# 4_ADC_schdoc.net
KiCad netlist of a schematic drawn in Altium Designer
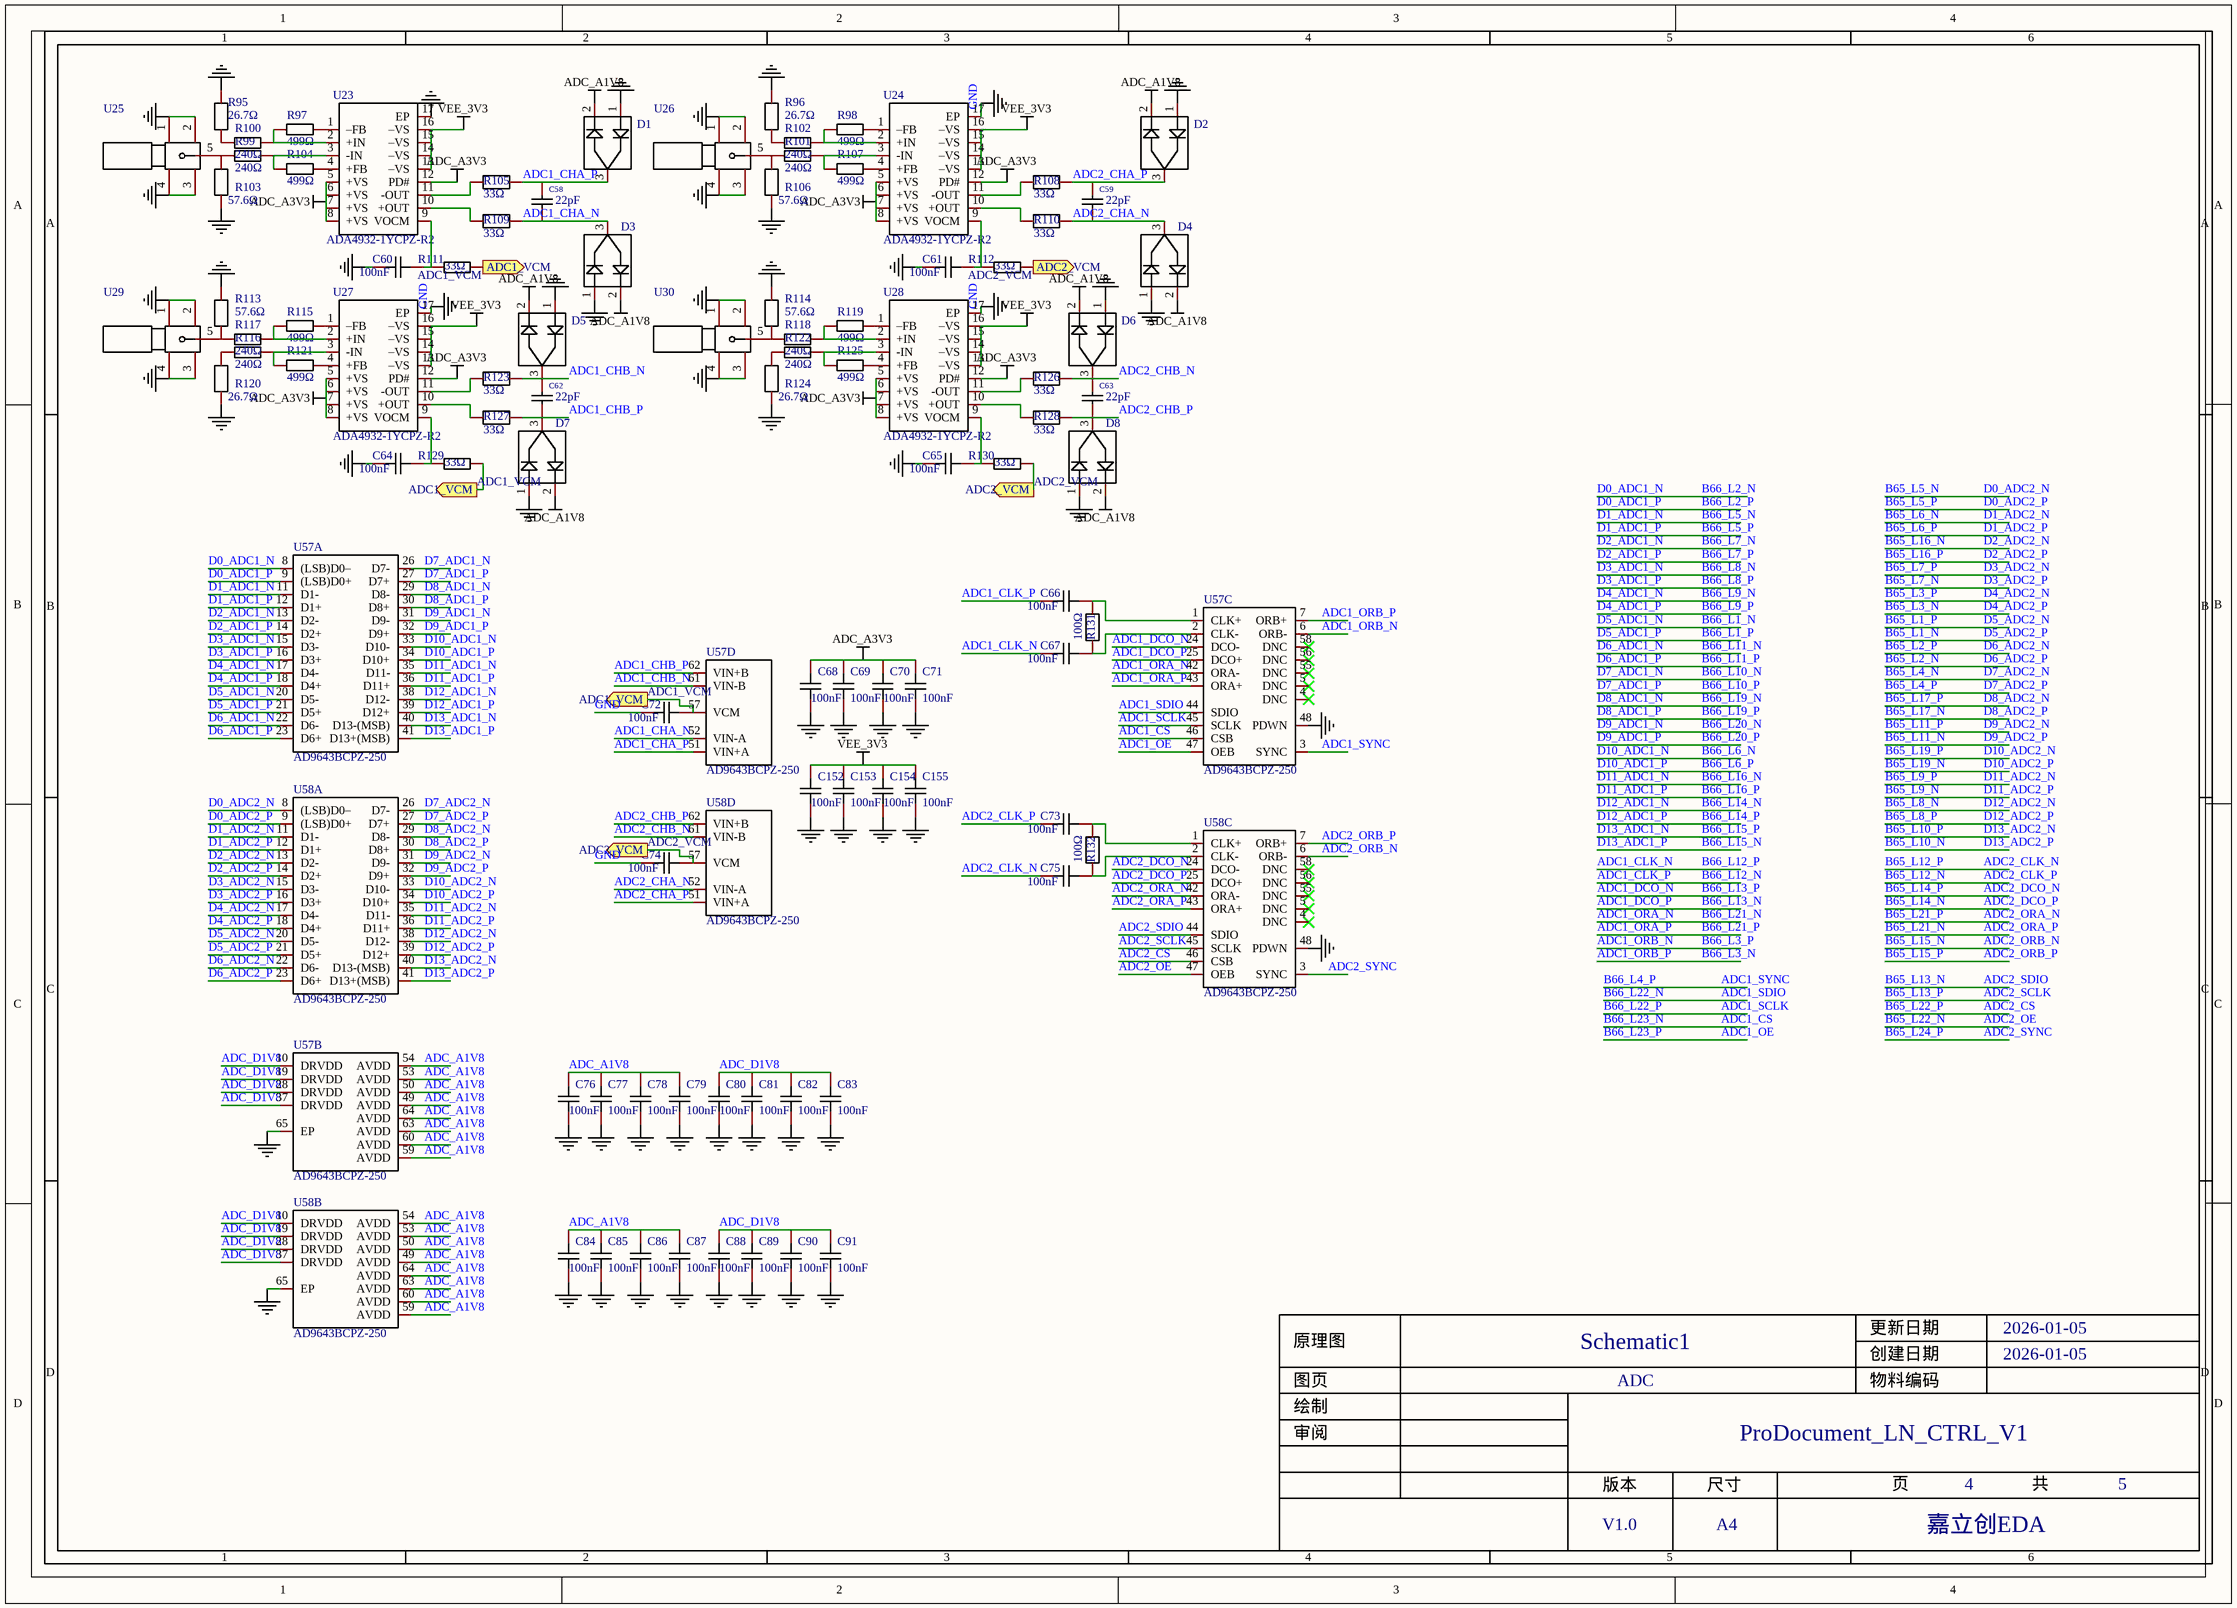
[diagram p0: 4_ADC.schdoc.schdoc]

(export (version "E")
  (design (tool "Eeschema 10.0.6"))
  (components
    (comp (ref "C58")
      (value "22pF")
      (fields
        (field (name "NAME") "22pF")
        (field (name "MANUFACTURER") "FH(风华)")
        (field (name "MANUFACTURER PART") "0402CG220J500NT")
        (field (name "TOLERANCE") "±5%")
      )
      (libsource (lib "altium-import") (part "root_1_0402CG220J500NT_"))
    )
    (comp (ref "C59")
      (value "22pF")
      (fields
        (field (name "NAME") "22pF")
        (field (name "MANUFACTURER") "FH(风华)")
        (field (name "MANUFACTURER PART") "0402CG220J500NT")
        (field (name "TOLERANCE") "±5%")
      )
      (libsource (lib "altium-import") (part "root_1_0402CG220J500NT_"))
    )
    (comp (ref "C60")
      (value "100nF")
      (fields
        (field (name "NAME") "100nF")
        (field (name "MANUFACTURER") "muRata(村田)")
        (field (name "MANUFACTURER PART") "GRM155R71H104KE14D")
        (field (name "TOLERANCE") "±10%")
      )
      (libsource (lib "altium-import") (part "root_2_GRM155R71H104KE14D_"))
    )
    (comp (ref "C61")
      (value "100nF")
      (fields
        (field (name "NAME") "100nF")
        (field (name "MANUFACTURER") "muRata(村田)")
        (field (name "MANUFACTURER PART") "GRM155R71H104KE14D")
        (field (name "TOLERANCE") "±10%")
      )
      (libsource (lib "altium-import") (part "root_2_GRM155R71H104KE14D_"))
    )
    (comp (ref "C62")
      (value "22pF")
      (fields
        (field (name "NAME") "22pF")
        (field (name "MANUFACTURER") "FH(风华)")
        (field (name "MANUFACTURER PART") "0402CG220J500NT")
        (field (name "TOLERANCE") "±5%")
      )
      (libsource (lib "altium-import") (part "root_1_0402CG220J500NT_"))
    )
    (comp (ref "C63")
      (value "22pF")
      (fields
        (field (name "NAME") "22pF")
        (field (name "MANUFACTURER") "FH(风华)")
        (field (name "MANUFACTURER PART") "0402CG220J500NT")
        (field (name "TOLERANCE") "±5%")
      )
      (libsource (lib "altium-import") (part "root_1_0402CG220J500NT_"))
    )
    (comp (ref "C64")
      (value "100nF")
      (fields
        (field (name "NAME") "100nF")
        (field (name "MANUFACTURER") "muRata(村田)")
        (field (name "MANUFACTURER PART") "GRM155R71H104KE14D")
        (field (name "TOLERANCE") "±10%")
      )
      (libsource (lib "altium-import") (part "root_2_GRM155R71H104KE14D_"))
    )
    (comp (ref "C65")
      (value "100nF")
      (fields
        (field (name "NAME") "100nF")
        (field (name "MANUFACTURER") "muRata(村田)")
        (field (name "MANUFACTURER PART") "GRM155R71H104KE14D")
        (field (name "TOLERANCE") "±10%")
      )
      (libsource (lib "altium-import") (part "root_2_GRM155R71H104KE14D_"))
    )
    (comp (ref "C66")
      (value "100nF")
      (fields
        (field (name "NAME") "100nF")
        (field (name "MANUFACTURER") "muRata(村田)")
        (field (name "MANUFACTURER PART") "GRM155R71H104KE14D")
        (field (name "TOLERANCE") "±10%")
      )
      (libsource (lib "altium-import") (part "root_2_GRM155R71H104KE14D_"))
    )
    (comp (ref "C67")
      (value "100nF")
      (fields
        (field (name "NAME") "100nF")
        (field (name "MANUFACTURER") "muRata(村田)")
        (field (name "MANUFACTURER PART") "GRM155R71H104KE14D")
        (field (name "TOLERANCE") "±10%")
      )
      (libsource (lib "altium-import") (part "root_2_GRM155R71H104KE14D_"))
    )
    (comp (ref "C68")
      (value "100nF")
      (fields
        (field (name "NAME") "100nF")
        (field (name "MANUFACTURER") "muRata(村田)")
        (field (name "MANUFACTURER PART") "GRM155R71H104KE14D")
        (field (name "TOLERANCE") "±10%")
      )
      (libsource (lib "altium-import") (part "root_1_GRM155R71H104KE14D_"))
    )
    (comp (ref "C69")
      (value "100nF")
      (fields
        (field (name "NAME") "100nF")
        (field (name "MANUFACTURER") "muRata(村田)")
        (field (name "MANUFACTURER PART") "GRM155R71H104KE14D")
        (field (name "TOLERANCE") "±10%")
      )
      (libsource (lib "altium-import") (part "root_1_GRM155R71H104KE14D_"))
    )
    (comp (ref "C70")
      (value "100nF")
      (fields
        (field (name "NAME") "100nF")
        (field (name "MANUFACTURER") "muRata(村田)")
        (field (name "MANUFACTURER PART") "GRM155R71H104KE14D")
        (field (name "TOLERANCE") "±10%")
      )
      (libsource (lib "altium-import") (part "root_1_GRM155R71H104KE14D_"))
    )
    (comp (ref "C71")
      (value "100nF")
      (fields
        (field (name "NAME") "100nF")
        (field (name "MANUFACTURER") "muRata(村田)")
        (field (name "MANUFACTURER PART") "GRM155R71H104KE14D")
        (field (name "TOLERANCE") "±10%")
      )
      (libsource (lib "altium-import") (part "root_1_GRM155R71H104KE14D_"))
    )
    (comp (ref "C72")
      (value "100nF")
      (fields
        (field (name "NAME") "100nF")
        (field (name "MANUFACTURER") "muRata(村田)")
        (field (name "MANUFACTURER PART") "GRM155R71H104KE14D")
        (field (name "TOLERANCE") "±10%")
      )
      (libsource (lib "altium-import") (part "root_2_GRM155R71H104KE14D_"))
    )
    (comp (ref "C73")
      (value "100nF")
      (fields
        (field (name "NAME") "100nF")
        (field (name "MANUFACTURER") "muRata(村田)")
        (field (name "MANUFACTURER PART") "GRM155R71H104KE14D")
        (field (name "TOLERANCE") "±10%")
      )
      (libsource (lib "altium-import") (part "root_2_GRM155R71H104KE14D_"))
    )
    (comp (ref "C74")
      (value "100nF")
      (fields
        (field (name "NAME") "100nF")
        (field (name "MANUFACTURER") "muRata(村田)")
        (field (name "MANUFACTURER PART") "GRM155R71H104KE14D")
        (field (name "TOLERANCE") "±10%")
      )
      (libsource (lib "altium-import") (part "root_2_GRM155R71H104KE14D_"))
    )
    (comp (ref "C75")
      (value "100nF")
      (fields
        (field (name "NAME") "100nF")
        (field (name "MANUFACTURER") "muRata(村田)")
        (field (name "MANUFACTURER PART") "GRM155R71H104KE14D")
        (field (name "TOLERANCE") "±10%")
      )
      (libsource (lib "altium-import") (part "root_2_GRM155R71H104KE14D_"))
    )
    (comp (ref "C76")
      (value "100nF")
      (fields
        (field (name "NAME") "100nF")
        (field (name "MANUFACTURER") "muRata(村田)")
        (field (name "MANUFACTURER PART") "GRM155R71H104KE14D")
        (field (name "TOLERANCE") "±10%")
      )
      (libsource (lib "altium-import") (part "root_1_GRM155R71H104KE14D_"))
    )
    (comp (ref "C77")
      (value "100nF")
      (fields
        (field (name "NAME") "100nF")
        (field (name "MANUFACTURER") "muRata(村田)")
        (field (name "MANUFACTURER PART") "GRM155R71H104KE14D")
        (field (name "TOLERANCE") "±10%")
      )
      (libsource (lib "altium-import") (part "root_1_GRM155R71H104KE14D_"))
    )
    (comp (ref "C78")
      (value "100nF")
      (fields
        (field (name "NAME") "100nF")
        (field (name "MANUFACTURER") "muRata(村田)")
        (field (name "MANUFACTURER PART") "GRM155R71H104KE14D")
        (field (name "TOLERANCE") "±10%")
      )
      (libsource (lib "altium-import") (part "root_1_GRM155R71H104KE14D_"))
    )
    (comp (ref "C79")
      (value "100nF")
      (fields
        (field (name "NAME") "100nF")
        (field (name "MANUFACTURER") "muRata(村田)")
        (field (name "MANUFACTURER PART") "GRM155R71H104KE14D")
        (field (name "TOLERANCE") "±10%")
      )
      (libsource (lib "altium-import") (part "root_1_GRM155R71H104KE14D_"))
    )
    (comp (ref "C80")
      (value "100nF")
      (fields
        (field (name "NAME") "100nF")
        (field (name "MANUFACTURER") "muRata(村田)")
        (field (name "MANUFACTURER PART") "GRM155R71H104KE14D")
        (field (name "TOLERANCE") "±10%")
      )
      (libsource (lib "altium-import") (part "root_1_GRM155R71H104KE14D_"))
    )
    (comp (ref "C81")
      (value "100nF")
      (fields
        (field (name "NAME") "100nF")
        (field (name "MANUFACTURER") "muRata(村田)")
        (field (name "MANUFACTURER PART") "GRM155R71H104KE14D")
        (field (name "TOLERANCE") "±10%")
      )
      (libsource (lib "altium-import") (part "root_1_GRM155R71H104KE14D_"))
    )
    (comp (ref "C82")
      (value "100nF")
      (fields
        (field (name "NAME") "100nF")
        (field (name "MANUFACTURER") "muRata(村田)")
        (field (name "MANUFACTURER PART") "GRM155R71H104KE14D")
        (field (name "TOLERANCE") "±10%")
      )
      (libsource (lib "altium-import") (part "root_1_GRM155R71H104KE14D_"))
    )
    (comp (ref "C83")
      (value "100nF")
      (fields
        (field (name "NAME") "100nF")
        (field (name "MANUFACTURER") "muRata(村田)")
        (field (name "MANUFACTURER PART") "GRM155R71H104KE14D")
        (field (name "TOLERANCE") "±10%")
      )
      (libsource (lib "altium-import") (part "root_1_GRM155R71H104KE14D_"))
    )
    (comp (ref "C84")
      (value "100nF")
      (fields
        (field (name "NAME") "100nF")
        (field (name "MANUFACTURER") "muRata(村田)")
        (field (name "MANUFACTURER PART") "GRM155R71H104KE14D")
        (field (name "TOLERANCE") "±10%")
      )
      (libsource (lib "altium-import") (part "root_1_GRM155R71H104KE14D_"))
    )
    (comp (ref "C85")
      (value "100nF")
      (fields
        (field (name "NAME") "100nF")
        (field (name "MANUFACTURER") "muRata(村田)")
        (field (name "MANUFACTURER PART") "GRM155R71H104KE14D")
        (field (name "TOLERANCE") "±10%")
      )
      (libsource (lib "altium-import") (part "root_1_GRM155R71H104KE14D_"))
    )
    (comp (ref "C86")
      (value "100nF")
      (fields
        (field (name "NAME") "100nF")
        (field (name "MANUFACTURER") "muRata(村田)")
        (field (name "MANUFACTURER PART") "GRM155R71H104KE14D")
        (field (name "TOLERANCE") "±10%")
      )
      (libsource (lib "altium-import") (part "root_1_GRM155R71H104KE14D_"))
    )
    (comp (ref "C87")
      (value "100nF")
      (fields
        (field (name "NAME") "100nF")
        (field (name "MANUFACTURER") "muRata(村田)")
        (field (name "MANUFACTURER PART") "GRM155R71H104KE14D")
        (field (name "TOLERANCE") "±10%")
      )
      (libsource (lib "altium-import") (part "root_1_GRM155R71H104KE14D_"))
    )
    (comp (ref "C88")
      (value "100nF")
      (fields
        (field (name "NAME") "100nF")
        (field (name "MANUFACTURER") "muRata(村田)")
        (field (name "MANUFACTURER PART") "GRM155R71H104KE14D")
        (field (name "TOLERANCE") "±10%")
      )
      (libsource (lib "altium-import") (part "root_1_GRM155R71H104KE14D_"))
    )
    (comp (ref "C89")
      (value "100nF")
      (fields
        (field (name "NAME") "100nF")
        (field (name "MANUFACTURER") "muRata(村田)")
        (field (name "MANUFACTURER PART") "GRM155R71H104KE14D")
        (field (name "TOLERANCE") "±10%")
      )
      (libsource (lib "altium-import") (part "root_1_GRM155R71H104KE14D_"))
    )
    (comp (ref "C90")
      (value "100nF")
      (fields
        (field (name "NAME") "100nF")
        (field (name "MANUFACTURER") "muRata(村田)")
        (field (name "MANUFACTURER PART") "GRM155R71H104KE14D")
        (field (name "TOLERANCE") "±10%")
      )
      (libsource (lib "altium-import") (part "root_1_GRM155R71H104KE14D_"))
    )
    (comp (ref "C91")
      (value "100nF")
      (fields
        (field (name "NAME") "100nF")
        (field (name "MANUFACTURER") "muRata(村田)")
        (field (name "MANUFACTURER PART") "GRM155R71H104KE14D")
        (field (name "TOLERANCE") "±10%")
      )
      (libsource (lib "altium-import") (part "root_1_GRM155R71H104KE14D_"))
    )
    (comp (ref "C152")
      (value "100nF")
      (fields
        (field (name "NAME") "100nF")
        (field (name "MANUFACTURER") "muRata(村田)")
        (field (name "MANUFACTURER PART") "GRM155R71H104KE14D")
        (field (name "TOLERANCE") "±10%")
      )
      (libsource (lib "altium-import") (part "root_1_GRM155R71H104KE14D_"))
    )
    (comp (ref "C153")
      (value "100nF")
      (fields
        (field (name "NAME") "100nF")
        (field (name "MANUFACTURER") "muRata(村田)")
        (field (name "MANUFACTURER PART") "GRM155R71H104KE14D")
        (field (name "TOLERANCE") "±10%")
      )
      (libsource (lib "altium-import") (part "root_1_GRM155R71H104KE14D_"))
    )
    (comp (ref "C154")
      (value "100nF")
      (fields
        (field (name "NAME") "100nF")
        (field (name "MANUFACTURER") "muRata(村田)")
        (field (name "MANUFACTURER PART") "GRM155R71H104KE14D")
        (field (name "TOLERANCE") "±10%")
      )
      (libsource (lib "altium-import") (part "root_1_GRM155R71H104KE14D_"))
    )
    (comp (ref "C155")
      (value "100nF")
      (fields
        (field (name "NAME") "100nF")
        (field (name "MANUFACTURER") "muRata(村田)")
        (field (name "MANUFACTURER PART") "GRM155R71H104KE14D")
        (field (name "TOLERANCE") "±10%")
      )
      (libsource (lib "altium-import") (part "root_1_GRM155R71H104KE14D_"))
    )
    (comp (ref "D1")
      (value "NSVR351SDSA3T1G")
      (description "二极管配置:1对串联式;正向压降(Vf):230mV@1mA;直流反向耐压(Vr):5V;整流电流:30mA;")
      (fields (field (name "MANUFACTURER") "onsemi(安森美)"))
      (libsource (lib "altium-import") (part "root_3_NSVR351SDSA3T1G_"))
    )
    (comp (ref "D2")
      (value "NSVR351SDSA3T1G")
      (description "二极管配置:1对串联式;正向压降(Vf):230mV@1mA;直流反向耐压(Vr):5V;整流电流:30mA;")
      (fields (field (name "MANUFACTURER") "onsemi(安森美)"))
      (libsource (lib "altium-import") (part "root_3_NSVR351SDSA3T1G_"))
    )
    (comp (ref "D3")
      (value "NSVR351SDSA3T1G")
      (description "二极管配置:1对串联式;正向压降(Vf):230mV@1mA;直流反向耐压(Vr):5V;整流电流:30mA;")
      (fields (field (name "MANUFACTURER") "onsemi(安森美)"))
      (libsource (lib "altium-import") (part "root_1_NSVR351SDSA3T1G_"))
    )
    (comp (ref "D4")
      (value "NSVR351SDSA3T1G")
      (description "二极管配置:1对串联式;正向压降(Vf):230mV@1mA;直流反向耐压(Vr):5V;整流电流:30mA;")
      (fields (field (name "MANUFACTURER") "onsemi(安森美)"))
      (libsource (lib "altium-import") (part "root_1_NSVR351SDSA3T1G_"))
    )
    (comp (ref "D5")
      (value "NSVR351SDSA3T1G")
      (description "二极管配置:1对串联式;正向压降(Vf):230mV@1mA;直流反向耐压(Vr):5V;整流电流:30mA;")
      (fields (field (name "MANUFACTURER") "onsemi(安森美)"))
      (libsource (lib "altium-import") (part "root_3_NSVR351SDSA3T1G_"))
    )
    (comp (ref "D6")
      (value "NSVR351SDSA3T1G")
      (description "二极管配置:1对串联式;正向压降(Vf):230mV@1mA;直流反向耐压(Vr):5V;整流电流:30mA;")
      (fields (field (name "MANUFACTURER") "onsemi(安森美)"))
      (libsource (lib "altium-import") (part "root_3_NSVR351SDSA3T1G_"))
    )
    (comp (ref "D7")
      (value "NSVR351SDSA3T1G")
      (description "二极管配置:1对串联式;正向压降(Vf):230mV@1mA;直流反向耐压(Vr):5V;整流电流:30mA;")
      (fields (field (name "MANUFACTURER") "onsemi(安森美)"))
      (libsource (lib "altium-import") (part "root_1_NSVR351SDSA3T1G_"))
    )
    (comp (ref "D8")
      (value "NSVR351SDSA3T1G")
      (description "二极管配置:1对串联式;正向压降(Vf):230mV@1mA;直流反向耐压(Vr):5V;整流电流:30mA;")
      (fields (field (name "MANUFACTURER") "onsemi(安森美)"))
      (libsource (lib "altium-import") (part "root_1_NSVR351SDSA3T1G_"))
    )
    (comp (ref "R95")
      (value "26.7Ω")
      (description "阻值:1kΩ;精度:±0.1%;温度系数:±25ppm/;")
      (fields (field (name "MANUFACTURER") "Viking(光颉)") (field (name "MANUFACTURER PART") "ARG02BTC1001"))
      (libsource (lib "altium-import") (part "root_3_ARG02BTC1001_"))
    )
    (comp (ref "R96")
      (value "26.7Ω")
      (description "阻值:1kΩ;精度:±0.1%;温度系数:±25ppm/;")
      (fields (field (name "MANUFACTURER") "Viking(光颉)") (field (name "MANUFACTURER PART") "ARG02BTC1001"))
      (libsource (lib "altium-import") (part "root_1_ARG02BTC1001_"))
    )
    (comp (ref "R97")
      (value "499Ω")
      (fields
        (field (name "NAME") "499Ω")
        (field (name "MANUFACTURER") "UNI-ROYAL(厚声)")
        (field (name "MANUFACTURER PART") "0402WGF4990TCE")
        (field (name "TOLERANCE") "±1%")
      )
      (libsource (lib "altium-import") (part "root_0_0402WGF4990TCE_"))
    )
    (comp (ref "R98")
      (value "499Ω")
      (fields
        (field (name "NAME") "499Ω")
        (field (name "MANUFACTURER") "UNI-ROYAL(厚声)")
        (field (name "MANUFACTURER PART") "0402WGF4990TCE")
        (field (name "TOLERANCE") "±1%")
      )
      (libsource (lib "altium-import") (part "root_0_0402WGF4990TCE_"))
    )
    (comp (ref "R99")
      (value "240Ω")
      (fields
        (field (name "NAME") "240Ω")
        (field (name "MANUFACTURER") "UNI-ROYAL(厚声)")
        (field (name "MANUFACTURER PART") "0402WGF2400TCE")
        (field (name "TOLERANCE") "±1%")
      )
      (libsource (lib "altium-import") (part "root_0_0402WGF2400TCE_"))
    )
    (comp (ref "R100")
      (value "240Ω")
      (fields
        (field (name "NAME") "240Ω")
        (field (name "MANUFACTURER") "UNI-ROYAL(厚声)")
        (field (name "MANUFACTURER PART") "0402WGF2400TCE")
        (field (name "TOLERANCE") "±1%")
      )
      (libsource (lib "altium-import") (part "root_0_0402WGF2400TCE_"))
    )
    (comp (ref "R101")
      (value "240Ω")
      (fields
        (field (name "NAME") "240Ω")
        (field (name "MANUFACTURER") "UNI-ROYAL(厚声)")
        (field (name "MANUFACTURER PART") "0402WGF2400TCE")
        (field (name "TOLERANCE") "±1%")
      )
      (libsource (lib "altium-import") (part "root_0_0402WGF2400TCE_"))
    )
    (comp (ref "R102")
      (value "240Ω")
      (fields
        (field (name "NAME") "240Ω")
        (field (name "MANUFACTURER") "UNI-ROYAL(厚声)")
        (field (name "MANUFACTURER PART") "0402WGF2400TCE")
        (field (name "TOLERANCE") "±1%")
      )
      (libsource (lib "altium-import") (part "root_0_0402WGF2400TCE_"))
    )
    (comp (ref "R103")
      (value "57.6Ω")
      (description "阻值:1kΩ;精度:±0.1%;温度系数:±25ppm/;")
      (fields (field (name "MANUFACTURER") "Viking(光颉)") (field (name "MANUFACTURER PART") "ARG02BTC1001"))
      (libsource (lib "altium-import") (part "root_3_ARG02BTC1001_"))
    )
    (comp (ref "R104")
      (value "499Ω")
      (fields
        (field (name "NAME") "499Ω")
        (field (name "MANUFACTURER") "UNI-ROYAL(厚声)")
        (field (name "MANUFACTURER PART") "0402WGF4990TCE")
        (field (name "TOLERANCE") "±1%")
      )
      (libsource (lib "altium-import") (part "root_0_0402WGF4990TCE_"))
    )
    (comp (ref "R105")
      (value "33Ω")
      (description "阻值:1kΩ;精度:±0.1%;温度系数:±25ppm/;")
      (fields (field (name "MANUFACTURER") "Viking(光颉)") (field (name "MANUFACTURER PART") "ARG02BTC1001"))
      (libsource (lib "altium-import") (part "root_2_ARG02BTC1001_"))
    )
    (comp (ref "R106")
      (value "57.6Ω")
      (description "阻值:1kΩ;精度:±0.1%;温度系数:±25ppm/;")
      (fields (field (name "MANUFACTURER") "Viking(光颉)") (field (name "MANUFACTURER PART") "ARG02BTC1001"))
      (libsource (lib "altium-import") (part "root_1_ARG02BTC1001_"))
    )
    (comp (ref "R107")
      (value "499Ω")
      (fields
        (field (name "NAME") "499Ω")
        (field (name "MANUFACTURER") "UNI-ROYAL(厚声)")
        (field (name "MANUFACTURER PART") "0402WGF4990TCE")
        (field (name "TOLERANCE") "±1%")
      )
      (libsource (lib "altium-import") (part "root_0_0402WGF4990TCE_"))
    )
    (comp (ref "R108")
      (value "33Ω")
      (description "阻值:1kΩ;精度:±0.1%;温度系数:±25ppm/;")
      (fields (field (name "MANUFACTURER") "Viking(光颉)") (field (name "MANUFACTURER PART") "ARG02BTC1001"))
      (libsource (lib "altium-import") (part "root_2_ARG02BTC1001_"))
    )
    (comp (ref "R109")
      (value "33Ω")
      (description "阻值:1kΩ;精度:±0.1%;温度系数:±25ppm/;")
      (fields (field (name "MANUFACTURER") "Viking(光颉)") (field (name "MANUFACTURER PART") "ARG02BTC1001"))
      (libsource (lib "altium-import") (part "root_2_ARG02BTC1001_"))
    )
    (comp (ref "R110")
      (value "33Ω")
      (description "阻值:1kΩ;精度:±0.1%;温度系数:±25ppm/;")
      (fields (field (name "MANUFACTURER") "Viking(光颉)") (field (name "MANUFACTURER PART") "ARG02BTC1001"))
      (libsource (lib "altium-import") (part "root_2_ARG02BTC1001_"))
    )
    (comp (ref "R111")
      (value "33Ω")
      (fields
        (field (name "NAME") "33Ω")
        (field (name "MANUFACTURER") "UNI-ROYAL(厚声)")
        (field (name "MANUFACTURER PART") "0402WGF330JTCE")
        (field (name "TOLERANCE") "±1%")
      )
      (libsource (lib "altium-import") (part "root_0_0402WGF330JTCE_"))
    )
    (comp (ref "R112")
      (value "33Ω")
      (fields
        (field (name "NAME") "33Ω")
        (field (name "MANUFACTURER") "UNI-ROYAL(厚声)")
        (field (name "MANUFACTURER PART") "0402WGF330JTCE")
        (field (name "TOLERANCE") "±1%")
      )
      (libsource (lib "altium-import") (part "root_0_0402WGF330JTCE_"))
    )
    (comp (ref "R113")
      (value "57.6Ω")
      (description "阻值:1kΩ;精度:±0.1%;温度系数:±25ppm/;")
      (fields (field (name "MANUFACTURER") "Viking(光颉)") (field (name "MANUFACTURER PART") "ARG02BTC1001"))
      (libsource (lib "altium-import") (part "root_1_ARG02BTC1001_"))
    )
    (comp (ref "R114")
      (value "57.6Ω")
      (description "阻值:1kΩ;精度:±0.1%;温度系数:±25ppm/;")
      (fields (field (name "MANUFACTURER") "Viking(光颉)") (field (name "MANUFACTURER PART") "ARG02BTC1001"))
      (libsource (lib "altium-import") (part "root_1_ARG02BTC1001_"))
    )
    (comp (ref "R115")
      (value "499Ω")
      (fields
        (field (name "NAME") "499Ω")
        (field (name "MANUFACTURER") "UNI-ROYAL(厚声)")
        (field (name "MANUFACTURER PART") "0402WGF4990TCE")
        (field (name "TOLERANCE") "±1%")
      )
      (libsource (lib "altium-import") (part "root_0_0402WGF4990TCE_"))
    )
    (comp (ref "R116")
      (value "240Ω")
      (fields
        (field (name "NAME") "240Ω")
        (field (name "MANUFACTURER") "UNI-ROYAL(厚声)")
        (field (name "MANUFACTURER PART") "0402WGF2400TCE")
        (field (name "TOLERANCE") "±1%")
      )
      (libsource (lib "altium-import") (part "root_0_0402WGF2400TCE_"))
    )
    (comp (ref "R117")
      (value "240Ω")
      (fields
        (field (name "NAME") "240Ω")
        (field (name "MANUFACTURER") "UNI-ROYAL(厚声)")
        (field (name "MANUFACTURER PART") "0402WGF2400TCE")
        (field (name "TOLERANCE") "±1%")
      )
      (libsource (lib "altium-import") (part "root_0_0402WGF2400TCE_"))
    )
    (comp (ref "R118")
      (value "240Ω")
      (fields
        (field (name "NAME") "240Ω")
        (field (name "MANUFACTURER") "UNI-ROYAL(厚声)")
        (field (name "MANUFACTURER PART") "0402WGF2400TCE")
        (field (name "TOLERANCE") "±1%")
      )
      (libsource (lib "altium-import") (part "root_0_0402WGF2400TCE_"))
    )
    (comp (ref "R119")
      (value "499Ω")
      (fields
        (field (name "NAME") "499Ω")
        (field (name "MANUFACTURER") "UNI-ROYAL(厚声)")
        (field (name "MANUFACTURER PART") "0402WGF4990TCE")
        (field (name "TOLERANCE") "±1%")
      )
      (libsource (lib "altium-import") (part "root_0_0402WGF4990TCE_"))
    )
    (comp (ref "R120")
      (value "26.7Ω")
      (description "阻值:1kΩ;精度:±0.1%;温度系数:±25ppm/;")
      (fields (field (name "MANUFACTURER") "Viking(光颉)") (field (name "MANUFACTURER PART") "ARG02BTC1001"))
      (libsource (lib "altium-import") (part "root_1_ARG02BTC1001_"))
    )
    (comp (ref "R121")
      (value "499Ω")
      (fields
        (field (name "NAME") "499Ω")
        (field (name "MANUFACTURER") "UNI-ROYAL(厚声)")
        (field (name "MANUFACTURER PART") "0402WGF4990TCE")
        (field (name "TOLERANCE") "±1%")
      )
      (libsource (lib "altium-import") (part "root_0_0402WGF4990TCE_"))
    )
    (comp (ref "R122")
      (value "240Ω")
      (fields
        (field (name "NAME") "240Ω")
        (field (name "MANUFACTURER") "UNI-ROYAL(厚声)")
        (field (name "MANUFACTURER PART") "0402WGF2400TCE")
        (field (name "TOLERANCE") "±1%")
      )
      (libsource (lib "altium-import") (part "root_0_0402WGF2400TCE_"))
    )
    (comp (ref "R123")
      (value "33Ω")
      (description "阻值:1kΩ;精度:±0.1%;温度系数:±25ppm/;")
      (fields (field (name "MANUFACTURER") "Viking(光颉)") (field (name "MANUFACTURER PART") "ARG02BTC1001"))
      (libsource (lib "altium-import") (part "root_2_ARG02BTC1001_"))
    )
    (comp (ref "R124")
      (value "26.7Ω")
      (description "阻值:1kΩ;精度:±0.1%;温度系数:±25ppm/;")
      (fields (field (name "MANUFACTURER") "Viking(光颉)") (field (name "MANUFACTURER PART") "ARG02BTC1001"))
      (libsource (lib "altium-import") (part "root_1_ARG02BTC1001_"))
    )
    (comp (ref "R125")
      (value "499Ω")
      (fields
        (field (name "NAME") "499Ω")
        (field (name "MANUFACTURER") "UNI-ROYAL(厚声)")
        (field (name "MANUFACTURER PART") "0402WGF4990TCE")
        (field (name "TOLERANCE") "±1%")
      )
      (libsource (lib "altium-import") (part "root_0_0402WGF4990TCE_"))
    )
    (comp (ref "R126")
      (value "33Ω")
      (description "阻值:1kΩ;精度:±0.1%;温度系数:±25ppm/;")
      (fields (field (name "MANUFACTURER") "Viking(光颉)") (field (name "MANUFACTURER PART") "ARG02BTC1001"))
      (libsource (lib "altium-import") (part "root_2_ARG02BTC1001_"))
    )
    (comp (ref "R127")
      (value "33Ω")
      (description "阻值:1kΩ;精度:±0.1%;温度系数:±25ppm/;")
      (fields (field (name "MANUFACTURER") "Viking(光颉)") (field (name "MANUFACTURER PART") "ARG02BTC1001"))
      (libsource (lib "altium-import") (part "root_2_ARG02BTC1001_"))
    )
    (comp (ref "R128")
      (value "33Ω")
      (description "阻值:1kΩ;精度:±0.1%;温度系数:±25ppm/;")
      (fields (field (name "MANUFACTURER") "Viking(光颉)") (field (name "MANUFACTURER PART") "ARG02BTC1001"))
      (libsource (lib "altium-import") (part "root_2_ARG02BTC1001_"))
    )
    (comp (ref "R129")
      (value "33Ω")
      (fields
        (field (name "NAME") "33Ω")
        (field (name "MANUFACTURER") "UNI-ROYAL(厚声)")
        (field (name "MANUFACTURER PART") "0402WGF330JTCE")
        (field (name "TOLERANCE") "±1%")
      )
      (libsource (lib "altium-import") (part "root_0_0402WGF330JTCE_"))
    )
    (comp (ref "R130")
      (value "33Ω")
      (fields
        (field (name "NAME") "33Ω")
        (field (name "MANUFACTURER") "UNI-ROYAL(厚声)")
        (field (name "MANUFACTURER PART") "0402WGF330JTCE")
        (field (name "TOLERANCE") "±1%")
      )
      (libsource (lib "altium-import") (part "root_0_0402WGF330JTCE_"))
    )
    (comp (ref "R131")
      (value "100Ω")
      (fields
        (field (name "NAME") "100Ω")
        (field (name "MANUFACTURER") "YAGEO(国巨)")
        (field (name "MANUFACTURER PART") "RT0402BRD07100RL")
        (field (name "TOLERANCE") "±0.1%")
      )
      (libsource (lib "altium-import") (part "root_1_RT0402BRD07100RL_"))
    )
    (comp (ref "R132")
      (value "100Ω")
      (fields
        (field (name "NAME") "100Ω")
        (field (name "MANUFACTURER") "YAGEO(国巨)")
        (field (name "MANUFACTURER PART") "RT0402BRD07100RL")
        (field (name "TOLERANCE") "±0.1%")
      )
      (libsource (lib "altium-import") (part "root_1_RT0402BRD07100RL_"))
    )
    (comp (ref "U23")
      (value "ADA4932-1YCPZ-R2")
      (fields (field (name "NAME") "ADA4932-1YCPZ-R2") (field (name "MANUFACTURER") "ADI(亚德诺)"))
      (libsource (lib "altium-import") (part "root_0_ADA4932-1YCPZ-R2_"))
    )
    (comp (ref "U24")
      (value "ADA4932-1YCPZ-R2")
      (fields (field (name "NAME") "ADA4932-1YCPZ-R2") (field (name "MANUFACTURER") "ADI(亚德诺)"))
      (libsource (lib "altium-import") (part "root_0_ADA4932-1YCPZ-R2_"))
    )
    (comp (ref "U25")
      (value "MOLEX_SMA")
      (description "C296128")
      (libsource (lib "altium-import") (part "root_0_MOLEX_SMA_"))
    )
    (comp (ref "U26")
      (value "MOLEX_SMA")
      (description "C296128")
      (libsource (lib "altium-import") (part "root_0_MOLEX_SMA_"))
    )
    (comp (ref "U27")
      (value "ADA4932-1YCPZ-R2")
      (fields (field (name "NAME") "ADA4932-1YCPZ-R2") (field (name "MANUFACTURER") "ADI(亚德诺)"))
      (libsource (lib "altium-import") (part "root_0_ADA4932-1YCPZ-R2_"))
    )
    (comp (ref "U28")
      (value "ADA4932-1YCPZ-R2")
      (fields (field (name "NAME") "ADA4932-1YCPZ-R2") (field (name "MANUFACTURER") "ADI(亚德诺)"))
      (libsource (lib "altium-import") (part "root_0_ADA4932-1YCPZ-R2_"))
    )
    (comp (ref "U29")
      (value "MOLEX_SMA")
      (description "C296128")
      (libsource (lib "altium-import") (part "root_0_MOLEX_SMA_"))
    )
    (comp (ref "U30")
      (value "MOLEX_SMA")
      (description "C296128")
      (libsource (lib "altium-import") (part "root_0_MOLEX_SMA_"))
    )
    (comp (ref "U57")
      (value "AD9643BCPZ-250")
      (description "接口:并行;电源电压:1.7V~1.9V;采样率:250MHz;分辨率:14;")
      (fields (field (name "NAME") "AD9643BCPZ-250") (field (name "MANUFACTURER") "ADI(亚德诺)"))
      (libsource (lib "altium-import") (part "root_0_AD9643BCPZ-250_"))
    )
    (comp (ref "U58")
      (value "AD9643BCPZ-250")
      (description "接口:并行;电源电压:1.7V~1.9V;采样率:250MHz;分辨率:14;")
      (fields (field (name "NAME") "AD9643BCPZ-250") (field (name "MANUFACTURER") "ADI(亚德诺)"))
      (libsource (lib "altium-import") (part "root_0_AD9643BCPZ-250_"))
    )
  )
  (nets
    (net (code "1") (name "/ADC1_CHA_N") (class "Default")
      (node (ref "C58") (pin "1") (pinfunction "1_1") (pintype "passive"))
      (node (ref "D3") (pin "3") (pinfunction "Anode/Cathode_3") (pintype "passive"))
      (node (ref "R109") (pin "1") (pinfunction "1_1") (pintype "passive"))
      (node (ref "U57") (pin "52") (pinfunction "VIN-A_52") (pintype "passive"))
    )
    (net (code "2") (name "/ADC1_CHA_P") (class "Default")
      (node (ref "C58") (pin "2") (pinfunction "2_2") (pintype "passive"))
      (node (ref "D1") (pin "3") (pinfunction "Anode/Cathode_3") (pintype "passive"))
      (node (ref "R105") (pin "1") (pinfunction "1_1") (pintype "passive"))
      (node (ref "U57") (pin "51") (pinfunction "VIN+A_51") (pintype "passive"))
    )
    (net (code "3") (name "/ADC1_CHB_N") (class "Default")
      (node (ref "C62") (pin "2") (pinfunction "2_2") (pintype "passive"))
      (node (ref "D5") (pin "3") (pinfunction "Anode/Cathode_3") (pintype "passive"))
      (node (ref "R123") (pin "1") (pinfunction "1_1") (pintype "passive"))
      (node (ref "U57") (pin "61") (pinfunction "VIN-B_61") (pintype "passive"))
    )
    (net (code "4") (name "/ADC1_CHB_P") (class "Default")
      (node (ref "C62") (pin "1") (pinfunction "1_1") (pintype "passive"))
      (node (ref "D7") (pin "3") (pinfunction "Anode/Cathode_3") (pintype "passive"))
      (node (ref "R127") (pin "1") (pinfunction "1_1") (pintype "passive"))
      (node (ref "U57") (pin "62") (pinfunction "VIN+B_62") (pintype "passive"))
    )
    (net (code "5") (name "/ADC1_CLK_N") (class "Default")
      (node (ref "C67") (pin "2") (pinfunction "2_2") (pintype "passive"))
    )
    (net (code "6") (name "/ADC1_CLK_P") (class "Default")
      (node (ref "C66") (pin "2") (pinfunction "2_2") (pintype "passive"))
    )
    (net (code "7") (name "/ADC1_CS") (class "Default")
      (node (ref "U57") (pin "46") (pinfunction "CSB_46") (pintype "passive"))
    )
    (net (code "8") (name "/ADC1_DCO_N") (class "Default")
      (node (ref "U57") (pin "24") (pinfunction "DCO-_24") (pintype "passive"))
    )
    (net (code "9") (name "/ADC1_DCO_P") (class "Default")
      (node (ref "U57") (pin "25") (pinfunction "DCO+_25") (pintype "passive"))
    )
    (net (code "10") (name "/ADC1_OE") (class "Default")
      (node (ref "U57") (pin "47") (pinfunction "OEB_47") (pintype "passive"))
    )
    (net (code "11") (name "/ADC1_ORA_N") (class "Default")
      (node (ref "U57") (pin "42") (pinfunction "ORA-_42") (pintype "passive"))
    )
    (net (code "12") (name "/ADC1_ORA_P") (class "Default")
      (node (ref "U57") (pin "43") (pinfunction "ORA+_43") (pintype "passive"))
    )
    (net (code "13") (name "/ADC1_ORB_N") (class "Default")
      (node (ref "U57") (pin "6") (pinfunction "ORB-_6") (pintype "passive"))
    )
    (net (code "14") (name "/ADC1_ORB_P") (class "Default")
      (node (ref "U57") (pin "7") (pinfunction "ORB+_7") (pintype "passive"))
    )
    (net (code "15") (name "/ADC1_SCLK") (class "Default")
      (node (ref "U57") (pin "45") (pinfunction "SCLK_45") (pintype "passive"))
    )
    (net (code "16") (name "/ADC1_SDIO") (class "Default")
      (node (ref "U57") (pin "44") (pinfunction "SDIO_44") (pintype "passive"))
    )
    (net (code "17") (name "/ADC1_SYNC") (class "Default")
      (node (ref "U57") (pin "3") (pinfunction "SYNC_3") (pintype "passive"))
    )
    (net (code "18") (name "/ADC1_VCM") (class "Default")
      (node (ref "C72") (pin "1") (pinfunction "1_1") (pintype "passive"))
      (node (ref "R111") (pin "2") (pinfunction "2_2") (pintype "passive"))
      (node (ref "R129") (pin "2") (pinfunction "2_2") (pintype "passive"))
      (node (ref "U57") (pin "57") (pinfunction "VCM_57") (pintype "passive"))
    )
    (net (code "19") (name "/ADC2_CHA_N") (class "Default")
      (node (ref "C59") (pin "1") (pinfunction "1_1") (pintype "passive"))
      (node (ref "D4") (pin "3") (pinfunction "Anode/Cathode_3") (pintype "passive"))
      (node (ref "R110") (pin "1") (pinfunction "1_1") (pintype "passive"))
      (node (ref "U58") (pin "52") (pinfunction "VIN-A_52") (pintype "passive"))
    )
    (net (code "20") (name "/ADC2_CHA_P") (class "Default")
      (node (ref "C59") (pin "2") (pinfunction "2_2") (pintype "passive"))
      (node (ref "D2") (pin "3") (pinfunction "Anode/Cathode_3") (pintype "passive"))
      (node (ref "R108") (pin "1") (pinfunction "1_1") (pintype "passive"))
      (node (ref "U58") (pin "51") (pinfunction "VIN+A_51") (pintype "passive"))
    )
    (net (code "21") (name "/ADC2_CHB_N") (class "Default")
      (node (ref "C63") (pin "2") (pinfunction "2_2") (pintype "passive"))
      (node (ref "D6") (pin "3") (pinfunction "Anode/Cathode_3") (pintype "passive"))
      (node (ref "R126") (pin "1") (pinfunction "1_1") (pintype "passive"))
      (node (ref "U58") (pin "61") (pinfunction "VIN-B_61") (pintype "passive"))
    )
    (net (code "22") (name "/ADC2_CHB_P") (class "Default")
      (node (ref "C63") (pin "1") (pinfunction "1_1") (pintype "passive"))
      (node (ref "D8") (pin "3") (pinfunction "Anode/Cathode_3") (pintype "passive"))
      (node (ref "R128") (pin "1") (pinfunction "1_1") (pintype "passive"))
      (node (ref "U58") (pin "62") (pinfunction "VIN+B_62") (pintype "passive"))
    )
    (net (code "23") (name "/ADC2_CLK_N") (class "Default")
      (node (ref "C75") (pin "2") (pinfunction "2_2") (pintype "passive"))
    )
    (net (code "24") (name "/ADC2_CLK_P") (class "Default")
      (node (ref "C73") (pin "2") (pinfunction "2_2") (pintype "passive"))
    )
    (net (code "25") (name "/ADC2_CS") (class "Default")
      (node (ref "U58") (pin "46") (pinfunction "CSB_46") (pintype "passive"))
    )
    (net (code "26") (name "/ADC2_DCO_N") (class "Default")
      (node (ref "U58") (pin "24") (pinfunction "DCO-_24") (pintype "passive"))
    )
    (net (code "27") (name "/ADC2_DCO_P") (class "Default")
      (node (ref "U58") (pin "25") (pinfunction "DCO+_25") (pintype "passive"))
    )
    (net (code "28") (name "/ADC2_OE") (class "Default")
      (node (ref "U58") (pin "47") (pinfunction "OEB_47") (pintype "passive"))
    )
    (net (code "29") (name "/ADC2_ORA_N") (class "Default")
      (node (ref "U58") (pin "42") (pinfunction "ORA-_42") (pintype "passive"))
    )
    (net (code "30") (name "/ADC2_ORA_P") (class "Default")
      (node (ref "U58") (pin "43") (pinfunction "ORA+_43") (pintype "passive"))
    )
    (net (code "31") (name "/ADC2_ORB_N") (class "Default")
      (node (ref "U58") (pin "6") (pinfunction "ORB-_6") (pintype "passive"))
    )
    (net (code "32") (name "/ADC2_ORB_P") (class "Default")
      (node (ref "U58") (pin "7") (pinfunction "ORB+_7") (pintype "passive"))
    )
    (net (code "33") (name "/ADC2_SCLK") (class "Default")
      (node (ref "U58") (pin "45") (pinfunction "SCLK_45") (pintype "passive"))
    )
    (net (code "34") (name "/ADC2_SDIO") (class "Default")
      (node (ref "U58") (pin "44") (pinfunction "SDIO_44") (pintype "passive"))
    )
    (net (code "35") (name "/ADC2_SYNC") (class "Default")
      (node (ref "U58") (pin "3") (pinfunction "SYNC_3") (pintype "passive"))
    )
    (net (code "36") (name "/ADC2_VCM") (class "Default")
      (node (ref "C74") (pin "1") (pinfunction "1_1") (pintype "passive"))
      (node (ref "R112") (pin "2") (pinfunction "2_2") (pintype "passive"))
      (node (ref "R130") (pin "2") (pinfunction "2_2") (pintype "passive"))
      (node (ref "U58") (pin "57") (pinfunction "VCM_57") (pintype "passive"))
    )
    (net (code "37") (name "/ADC_D1V8") (class "Default")
      (node (ref "C80") (pin "2") (pinfunction "2_2") (pintype "passive"))
      (node (ref "C81") (pin "2") (pinfunction "2_2") (pintype "passive"))
      (node (ref "C82") (pin "2") (pinfunction "2_2") (pintype "passive"))
      (node (ref "C83") (pin "2") (pinfunction "2_2") (pintype "passive"))
      (node (ref "C88") (pin "2") (pinfunction "2_2") (pintype "passive"))
      (node (ref "C89") (pin "2") (pinfunction "2_2") (pintype "passive"))
      (node (ref "C90") (pin "2") (pinfunction "2_2") (pintype "passive"))
      (node (ref "C91") (pin "2") (pinfunction "2_2") (pintype "passive"))
      (node (ref "U57") (pin "10") (pinfunction "DRVDD_10") (pintype "passive"))
      (node (ref "U57") (pin "19") (pinfunction "DRVDD_19") (pintype "passive"))
      (node (ref "U57") (pin "28") (pinfunction "DRVDD_28") (pintype "passive"))
      (node (ref "U57") (pin "37") (pinfunction "DRVDD_37") (pintype "passive"))
      (node (ref "U58") (pin "10") (pinfunction "DRVDD_10") (pintype "passive"))
      (node (ref "U58") (pin "19") (pinfunction "DRVDD_19") (pintype "passive"))
      (node (ref "U58") (pin "28") (pinfunction "DRVDD_28") (pintype "passive"))
      (node (ref "U58") (pin "37") (pinfunction "DRVDD_37") (pintype "passive"))
    )
    (net (code "38") (name "/B65_L1_N") (class "Default")
      (node (ref "U58") (pin "21") (pinfunction "D5+_21") (pintype "passive"))
    )
    (net (code "39") (name "/B65_L1_P") (class "Default")
      (node (ref "U58") (pin "20") (pinfunction "D5-_20") (pintype "passive"))
    )
    (net (code "40") (name "/B65_L2_N") (class "Default")
      (node (ref "U58") (pin "23") (pinfunction "D6+_23") (pintype "passive"))
    )
    (net (code "41") (name "/B65_L2_P") (class "Default")
      (node (ref "U58") (pin "22") (pinfunction "D6-_22") (pintype "passive"))
    )
    (net (code "42") (name "/B65_L3_N") (class "Default")
      (node (ref "U58") (pin "18") (pinfunction "D4+_18") (pintype "passive"))
    )
    (net (code "43") (name "/B65_L3_P") (class "Default")
      (node (ref "U58") (pin "17") (pinfunction "D4-_17") (pintype "passive"))
    )
    (net (code "44") (name "/B65_L4_N") (class "Default")
      (node (ref "U58") (pin "26") (pinfunction "D7-_26") (pintype "passive"))
    )
    (net (code "45") (name "/B65_L4_P") (class "Default")
      (node (ref "U58") (pin "27") (pinfunction "D7+_27") (pintype "passive"))
    )
    (net (code "46") (name "/B65_L5_N") (class "Default")
      (node (ref "U58") (pin "8") (pinfunction "(LSB)D0–_8") (pintype "passive"))
    )
    (net (code "47") (name "/B65_L5_P") (class "Default")
      (node (ref "U58") (pin "9") (pinfunction "(LSB)D0+_9") (pintype "passive"))
    )
    (net (code "48") (name "/B65_L6_N") (class "Default")
      (node (ref "U58") (pin "11") (pinfunction "D1-_11") (pintype "passive"))
    )
    (net (code "49") (name "/B65_L6_P") (class "Default")
      (node (ref "U58") (pin "12") (pinfunction "D1+_12") (pintype "passive"))
    )
    (net (code "50") (name "/B65_L7_N") (class "Default")
      (node (ref "U58") (pin "16") (pinfunction "D3+_16") (pintype "passive"))
    )
    (net (code "51") (name "/B65_L7_P") (class "Default")
      (node (ref "U58") (pin "15") (pinfunction "D3-_15") (pintype "passive"))
    )
    (net (code "52") (name "/B65_L8_N") (class "Default")
      (node (ref "U58") (pin "38") (pinfunction "D12-_38") (pintype "passive"))
    )
    (net (code "53") (name "/B65_L8_P") (class "Default")
      (node (ref "U58") (pin "39") (pinfunction "D12+_39") (pintype "passive"))
    )
    (net (code "54") (name "/B65_L9_N") (class "Default")
      (node (ref "U58") (pin "36") (pinfunction "D11+_36") (pintype "passive"))
    )
    (net (code "55") (name "/B65_L9_P") (class "Default")
      (node (ref "U58") (pin "35") (pinfunction "D11-_35") (pintype "passive"))
    )
    (net (code "56") (name "/B65_L10_N") (class "Default")
      (node (ref "U58") (pin "41") (pinfunction "D13+(MSB)_41") (pintype "passive"))
    )
    (net (code "57") (name "/B65_L10_P") (class "Default")
      (node (ref "U58") (pin "40") (pinfunction "D13-(MSB)_40") (pintype "passive"))
    )
    (net (code "58") (name "/B65_L11_N") (class "Default")
      (node (ref "U58") (pin "32") (pinfunction "D9+_32") (pintype "passive"))
    )
    (net (code "59") (name "/B65_L11_P") (class "Default")
      (node (ref "U58") (pin "31") (pinfunction "D9-_31") (pintype "passive"))
    )
    (net (code "60") (name "/B65_L16_N") (class "Default")
      (node (ref "U58") (pin "13") (pinfunction "D2-_13") (pintype "passive"))
    )
    (net (code "61") (name "/B65_L16_P") (class "Default")
      (node (ref "U58") (pin "14") (pinfunction "D2+_14") (pintype "passive"))
    )
    (net (code "62") (name "/B65_L17_N") (class "Default")
      (node (ref "U58") (pin "30") (pinfunction "D8+_30") (pintype "passive"))
    )
    (net (code "63") (name "/B65_L17_P") (class "Default")
      (node (ref "U58") (pin "29") (pinfunction "D8-_29") (pintype "passive"))
    )
    (net (code "64") (name "/B65_L19_N") (class "Default")
      (node (ref "U58") (pin "34") (pinfunction "D10+_34") (pintype "passive"))
    )
    (net (code "65") (name "/B65_L19_P") (class "Default")
      (node (ref "U58") (pin "33") (pinfunction "D10-_33") (pintype "passive"))
    )
    (net (code "66") (name "/B66_L1_N") (class "Default")
      (node (ref "U57") (pin "20") (pinfunction "D5-_20") (pintype "passive"))
    )
    (net (code "67") (name "/B66_L1_P") (class "Default")
      (node (ref "U57") (pin "21") (pinfunction "D5+_21") (pintype "passive"))
    )
    (net (code "68") (name "/B66_L2_N") (class "Default")
      (node (ref "U57") (pin "8") (pinfunction "(LSB)D0–_8") (pintype "passive"))
    )
    (net (code "69") (name "/B66_L2_P") (class "Default")
      (node (ref "U57") (pin "9") (pinfunction "(LSB)D0+_9") (pintype "passive"))
    )
    (net (code "70") (name "/B66_L5_N") (class "Default")
      (node (ref "U57") (pin "11") (pinfunction "D1-_11") (pintype "passive"))
    )
    (net (code "71") (name "/B66_L5_P") (class "Default")
      (node (ref "U57") (pin "12") (pinfunction "D1+_12") (pintype "passive"))
    )
    (net (code "72") (name "/B66_L6_N") (class "Default")
      (node (ref "U57") (pin "33") (pinfunction "D10-_33") (pintype "passive"))
    )
    (net (code "73") (name "/B66_L6_P") (class "Default")
      (node (ref "U57") (pin "34") (pinfunction "D10+_34") (pintype "passive"))
    )
    (net (code "74") (name "/B66_L7_N") (class "Default")
      (node (ref "U57") (pin "13") (pinfunction "D2-_13") (pintype "passive"))
    )
    (net (code "75") (name "/B66_L7_P") (class "Default")
      (node (ref "U57") (pin "14") (pinfunction "D2+_14") (pintype "passive"))
    )
    (net (code "76") (name "/B66_L8_N") (class "Default")
      (node (ref "U57") (pin "15") (pinfunction "D3-_15") (pintype "passive"))
    )
    (net (code "77") (name "/B66_L8_P") (class "Default")
      (node (ref "U57") (pin "16") (pinfunction "D3+_16") (pintype "passive"))
    )
    (net (code "78") (name "/B66_L9_N") (class "Default")
      (node (ref "U57") (pin "17") (pinfunction "D4-_17") (pintype "passive"))
    )
    (net (code "79") (name "/B66_L9_P") (class "Default")
      (node (ref "U57") (pin "18") (pinfunction "D4+_18") (pintype "passive"))
    )
    (net (code "80") (name "/B66_L10_N") (class "Default")
      (node (ref "U57") (pin "26") (pinfunction "D7-_26") (pintype "passive"))
    )
    (net (code "81") (name "/B66_L10_P") (class "Default")
      (node (ref "U57") (pin "27") (pinfunction "D7+_27") (pintype "passive"))
    )
    (net (code "82") (name "/B66_L11_N") (class "Default")
      (node (ref "U57") (pin "22") (pinfunction "D6-_22") (pintype "passive"))
    )
    (net (code "83") (name "/B66_L11_P") (class "Default")
      (node (ref "U57") (pin "23") (pinfunction "D6+_23") (pintype "passive"))
    )
    (net (code "84") (name "/B66_L14_N") (class "Default")
      (node (ref "U57") (pin "38") (pinfunction "D12-_38") (pintype "passive"))
    )
    (net (code "85") (name "/B66_L14_P") (class "Default")
      (node (ref "U57") (pin "39") (pinfunction "D12+_39") (pintype "passive"))
    )
    (net (code "86") (name "/B66_L15_N") (class "Default")
      (node (ref "U57") (pin "41") (pinfunction "D13+(MSB)_41") (pintype "passive"))
    )
    (net (code "87") (name "/B66_L15_P") (class "Default")
      (node (ref "U57") (pin "40") (pinfunction "D13-(MSB)_40") (pintype "passive"))
    )
    (net (code "88") (name "/B66_L16_N") (class "Default")
      (node (ref "U57") (pin "35") (pinfunction "D11-_35") (pintype "passive"))
    )
    (net (code "89") (name "/B66_L16_P") (class "Default")
      (node (ref "U57") (pin "36") (pinfunction "D11+_36") (pintype "passive"))
    )
    (net (code "90") (name "/B66_L19_N") (class "Default")
      (node (ref "U57") (pin "29") (pinfunction "D8-_29") (pintype "passive"))
    )
    (net (code "91") (name "/B66_L19_P") (class "Default")
      (node (ref "U57") (pin "30") (pinfunction "D8+_30") (pintype "passive"))
    )
    (net (code "92") (name "/B66_L20_N") (class "Default")
      (node (ref "U57") (pin "31") (pinfunction "D9-_31") (pintype "passive"))
    )
    (net (code "93") (name "/B66_L20_P") (class "Default")
      (node (ref "U57") (pin "32") (pinfunction "D9+_32") (pintype "passive"))
    )
    (net (code "94") (name "ADC_A1V8") (class "Default")
      (node (ref "C76") (pin "2") (pinfunction "2_2") (pintype "passive"))
      (node (ref "C77") (pin "2") (pinfunction "2_2") (pintype "passive"))
      (node (ref "C78") (pin "2") (pinfunction "2_2") (pintype "passive"))
      (node (ref "C79") (pin "2") (pinfunction "2_2") (pintype "passive"))
      (node (ref "C84") (pin "2") (pinfunction "2_2") (pintype "passive"))
      (node (ref "C85") (pin "2") (pinfunction "2_2") (pintype "passive"))
      (node (ref "C86") (pin "2") (pinfunction "2_2") (pintype "passive"))
      (node (ref "C87") (pin "2") (pinfunction "2_2") (pintype "passive"))
      (node (ref "D1") (pin "2") (pinfunction "Cathode_2") (pintype "passive"))
      (node (ref "D2") (pin "2") (pinfunction "Cathode_2") (pintype "passive"))
      (node (ref "D3") (pin "2") (pinfunction "Cathode_2") (pintype "passive"))
      (node (ref "D4") (pin "2") (pinfunction "Cathode_2") (pintype "passive"))
      (node (ref "D5") (pin "2") (pinfunction "Cathode_2") (pintype "passive"))
      (node (ref "D6") (pin "2") (pinfunction "Cathode_2") (pintype "passive"))
      (node (ref "D7") (pin "2") (pinfunction "Cathode_2") (pintype "passive"))
      (node (ref "D8") (pin "2") (pinfunction "Cathode_2") (pintype "passive"))
      (node (ref "U57") (pin "49") (pinfunction "AVDD_49") (pintype "passive"))
      (node (ref "U57") (pin "50") (pinfunction "AVDD_50") (pintype "passive"))
      (node (ref "U57") (pin "53") (pinfunction "AVDD_53") (pintype "passive"))
      (node (ref "U57") (pin "54") (pinfunction "AVDD_54") (pintype "passive"))
      (node (ref "U57") (pin "59") (pinfunction "AVDD_59") (pintype "passive"))
      (node (ref "U57") (pin "60") (pinfunction "AVDD_60") (pintype "passive"))
      (node (ref "U57") (pin "63") (pinfunction "AVDD_63") (pintype "passive"))
      (node (ref "U57") (pin "64") (pinfunction "AVDD_64") (pintype "passive"))
      (node (ref "U58") (pin "49") (pinfunction "AVDD_49") (pintype "passive"))
      (node (ref "U58") (pin "50") (pinfunction "AVDD_50") (pintype "passive"))
      (node (ref "U58") (pin "53") (pinfunction "AVDD_53") (pintype "passive"))
      (node (ref "U58") (pin "54") (pinfunction "AVDD_54") (pintype "passive"))
      (node (ref "U58") (pin "59") (pinfunction "AVDD_59") (pintype "passive"))
      (node (ref "U58") (pin "60") (pinfunction "AVDD_60") (pintype "passive"))
      (node (ref "U58") (pin "63") (pinfunction "AVDD_63") (pintype "passive"))
      (node (ref "U58") (pin "64") (pinfunction "AVDD_64") (pintype "passive"))
    )
    (net (code "95") (name "ADC_A3V3") (class "Default")
      (node (ref "C68") (pin "2") (pinfunction "2_2") (pintype "passive"))
      (node (ref "C69") (pin "2") (pinfunction "2_2") (pintype "passive"))
      (node (ref "C70") (pin "2") (pinfunction "2_2") (pintype "passive"))
      (node (ref "C71") (pin "2") (pinfunction "2_2") (pintype "passive"))
      (node (ref "U23") (pin "12") (pinfunction "PD#_12") (pintype "passive"))
      (node (ref "U23") (pin "5") (pinfunction "+VS_5") (pintype "passive"))
      (node (ref "U23") (pin "6") (pinfunction "+VS_6") (pintype "passive"))
      (node (ref "U23") (pin "7") (pinfunction "+VS_7") (pintype "passive"))
      (node (ref "U23") (pin "8") (pinfunction "+VS_8") (pintype "passive"))
      (node (ref "U24") (pin "12") (pinfunction "PD#_12") (pintype "passive"))
      (node (ref "U24") (pin "5") (pinfunction "+VS_5") (pintype "passive"))
      (node (ref "U24") (pin "6") (pinfunction "+VS_6") (pintype "passive"))
      (node (ref "U24") (pin "7") (pinfunction "+VS_7") (pintype "passive"))
      (node (ref "U24") (pin "8") (pinfunction "+VS_8") (pintype "passive"))
      (node (ref "U27") (pin "12") (pinfunction "PD#_12") (pintype "passive"))
      (node (ref "U27") (pin "5") (pinfunction "+VS_5") (pintype "passive"))
      (node (ref "U27") (pin "6") (pinfunction "+VS_6") (pintype "passive"))
      (node (ref "U27") (pin "7") (pinfunction "+VS_7") (pintype "passive"))
      (node (ref "U27") (pin "8") (pinfunction "+VS_8") (pintype "passive"))
      (node (ref "U28") (pin "12") (pinfunction "PD#_12") (pintype "passive"))
      (node (ref "U28") (pin "5") (pinfunction "+VS_5") (pintype "passive"))
      (node (ref "U28") (pin "6") (pinfunction "+VS_6") (pintype "passive"))
      (node (ref "U28") (pin "7") (pinfunction "+VS_7") (pintype "passive"))
      (node (ref "U28") (pin "8") (pinfunction "+VS_8") (pintype "passive"))
    )
    (net (code "96") (name "GND") (class "Default")
      (node (ref "C152") (pin "1") (pinfunction "1_1") (pintype "passive"))
      (node (ref "C153") (pin "1") (pinfunction "1_1") (pintype "passive"))
      (node (ref "C154") (pin "1") (pinfunction "1_1") (pintype "passive"))
      (node (ref "C155") (pin "1") (pinfunction "1_1") (pintype "passive"))
      (node (ref "C60") (pin "2") (pinfunction "2_2") (pintype "passive"))
      (node (ref "C61") (pin "2") (pinfunction "2_2") (pintype "passive"))
      (node (ref "C64") (pin "2") (pinfunction "2_2") (pintype "passive"))
      (node (ref "C65") (pin "2") (pinfunction "2_2") (pintype "passive"))
      (node (ref "C68") (pin "1") (pinfunction "1_1") (pintype "passive"))
      (node (ref "C69") (pin "1") (pinfunction "1_1") (pintype "passive"))
      (node (ref "C70") (pin "1") (pinfunction "1_1") (pintype "passive"))
      (node (ref "C71") (pin "1") (pinfunction "1_1") (pintype "passive"))
      (node (ref "C72") (pin "2") (pinfunction "2_2") (pintype "passive"))
      (node (ref "C74") (pin "2") (pinfunction "2_2") (pintype "passive"))
      (node (ref "C76") (pin "1") (pinfunction "1_1") (pintype "passive"))
      (node (ref "C77") (pin "1") (pinfunction "1_1") (pintype "passive"))
      (node (ref "C78") (pin "1") (pinfunction "1_1") (pintype "passive"))
      (node (ref "C79") (pin "1") (pinfunction "1_1") (pintype "passive"))
      (node (ref "C80") (pin "1") (pinfunction "1_1") (pintype "passive"))
      (node (ref "C81") (pin "1") (pinfunction "1_1") (pintype "passive"))
      (node (ref "C82") (pin "1") (pinfunction "1_1") (pintype "passive"))
      (node (ref "C83") (pin "1") (pinfunction "1_1") (pintype "passive"))
      (node (ref "C84") (pin "1") (pinfunction "1_1") (pintype "passive"))
      (node (ref "C85") (pin "1") (pinfunction "1_1") (pintype "passive"))
      (node (ref "C86") (pin "1") (pinfunction "1_1") (pintype "passive"))
      (node (ref "C87") (pin "1") (pinfunction "1_1") (pintype "passive"))
      (node (ref "C88") (pin "1") (pinfunction "1_1") (pintype "passive"))
      (node (ref "C89") (pin "1") (pinfunction "1_1") (pintype "passive"))
      (node (ref "C90") (pin "1") (pinfunction "1_1") (pintype "passive"))
      (node (ref "C91") (pin "1") (pinfunction "1_1") (pintype "passive"))
      (node (ref "D1") (pin "1") (pinfunction "Anode_1") (pintype "passive"))
      (node (ref "D2") (pin "1") (pinfunction "Anode_1") (pintype "passive"))
      (node (ref "D3") (pin "1") (pinfunction "Anode_1") (pintype "passive"))
      (node (ref "D4") (pin "1") (pinfunction "Anode_1") (pintype "passive"))
      (node (ref "D5") (pin "1") (pinfunction "Anode_1") (pintype "passive"))
      (node (ref "D6") (pin "1") (pinfunction "Anode_1") (pintype "passive"))
      (node (ref "D7") (pin "1") (pinfunction "Anode_1") (pintype "passive"))
      (node (ref "D8") (pin "1") (pinfunction "Anode_1") (pintype "passive"))
      (node (ref "R103") (pin "2") (pinfunction "2_2") (pintype "passive"))
      (node (ref "R106") (pin "1") (pinfunction "1_1") (pintype "passive"))
      (node (ref "R113") (pin "2") (pinfunction "2_2") (pintype "passive"))
      (node (ref "R114") (pin "2") (pinfunction "2_2") (pintype "passive"))
      (node (ref "R120") (pin "1") (pinfunction "1_1") (pintype "passive"))
      (node (ref "R124") (pin "1") (pinfunction "1_1") (pintype "passive"))
      (node (ref "R95") (pin "1") (pinfunction "1_1") (pintype "passive"))
      (node (ref "R96") (pin "2") (pinfunction "2_2") (pintype "passive"))
      (node (ref "U23") (pin "17") (pinfunction "EP_17") (pintype "passive"))
      (node (ref "U24") (pin "17") (pinfunction "EP_17") (pintype "passive"))
      (node (ref "U25") (pin "1") (pinfunction "1_1") (pintype "passive"))
      (node (ref "U25") (pin "2") (pinfunction "2_2") (pintype "passive"))
      (node (ref "U25") (pin "3") (pinfunction "3_3") (pintype "passive"))
      (node (ref "U25") (pin "4") (pinfunction "4_4") (pintype "passive"))
      (node (ref "U26") (pin "1") (pinfunction "1_1") (pintype "passive"))
      (node (ref "U26") (pin "2") (pinfunction "2_2") (pintype "passive"))
      (node (ref "U26") (pin "3") (pinfunction "3_3") (pintype "passive"))
      (node (ref "U26") (pin "4") (pinfunction "4_4") (pintype "passive"))
      (node (ref "U27") (pin "17") (pinfunction "EP_17") (pintype "passive"))
      (node (ref "U28") (pin "17") (pinfunction "EP_17") (pintype "passive"))
      (node (ref "U29") (pin "1") (pinfunction "1_1") (pintype "passive"))
      (node (ref "U29") (pin "2") (pinfunction "2_2") (pintype "passive"))
      (node (ref "U29") (pin "3") (pinfunction "3_3") (pintype "passive"))
      (node (ref "U29") (pin "4") (pinfunction "4_4") (pintype "passive"))
      (node (ref "U30") (pin "1") (pinfunction "1_1") (pintype "passive"))
      (node (ref "U30") (pin "2") (pinfunction "2_2") (pintype "passive"))
      (node (ref "U30") (pin "3") (pinfunction "3_3") (pintype "passive"))
      (node (ref "U30") (pin "4") (pinfunction "4_4") (pintype "passive"))
      (node (ref "U57") (pin "48") (pinfunction "PDWN_48") (pintype "passive"))
      (node (ref "U57") (pin "65") (pinfunction "EP_65") (pintype "passive"))
      (node (ref "U58") (pin "48") (pinfunction "PDWN_48") (pintype "passive"))
      (node (ref "U58") (pin "65") (pinfunction "EP_65") (pintype "passive"))
    )
    (net (code "97") (name "Net-(R100-Pad1)") (class "Default")
      (node (ref "R100") (pin "1") (pinfunction "1_1") (pintype "passive"))
      (node (ref "R95") (pin "2") (pinfunction "2_2") (pintype "passive"))
    )
    (net (code "98") (name "Net-(R101-Pad1)") (class "Default")
      (node (ref "R101") (pin "1") (pinfunction "1_1") (pintype "passive"))
      (node (ref "R106") (pin "2") (pinfunction "2_2") (pintype "passive"))
      (node (ref "U26") (pin "5") (pinfunction "5_5") (pintype "passive"))
    )
    (net (code "99") (name "Net-(R102-Pad1)") (class "Default")
      (node (ref "R102") (pin "1") (pinfunction "1_1") (pintype "passive"))
      (node (ref "R96") (pin "1") (pinfunction "1_1") (pintype "passive"))
    )
    (net (code "100") (name "Net-(R103-Pad1)") (class "Default")
      (node (ref "R103") (pin "1") (pinfunction "1_1") (pintype "passive"))
      (node (ref "R99") (pin "1") (pinfunction "1_1") (pintype "passive"))
      (node (ref "U25") (pin "5") (pinfunction "5_5") (pintype "passive"))
    )
    (net (code "101") (name "Net-(R113-Pad1)") (class "Default")
      (node (ref "R113") (pin "1") (pinfunction "1_1") (pintype "passive"))
      (node (ref "R117") (pin "1") (pinfunction "1_1") (pintype "passive"))
      (node (ref "U29") (pin "5") (pinfunction "5_5") (pintype "passive"))
    )
    (net (code "102") (name "Net-(R114-Pad1)") (class "Default")
      (node (ref "R114") (pin "1") (pinfunction "1_1") (pintype "passive"))
      (node (ref "R118") (pin "1") (pinfunction "1_1") (pintype "passive"))
      (node (ref "U30") (pin "5") (pinfunction "5_5") (pintype "passive"))
    )
    (net (code "103") (name "Net-(R116-Pad1)") (class "Default")
      (node (ref "R116") (pin "1") (pinfunction "1_1") (pintype "passive"))
      (node (ref "R120") (pin "2") (pinfunction "2_2") (pintype "passive"))
    )
    (net (code "104") (name "Net-(R122-Pad1)") (class "Default")
      (node (ref "R122") (pin "1") (pinfunction "1_1") (pintype "passive"))
      (node (ref "R124") (pin "2") (pinfunction "2_2") (pintype "passive"))
    )
    (net (code "105") (name "Net-(U23-+FB)") (class "Default")
      (node (ref "R104") (pin "2") (pinfunction "2_2") (pintype "passive"))
      (node (ref "U23") (pin "4") (pinfunction "+FB_4") (pintype "passive"))
    )
    (net (code "106") (name "Net-(U23-+IN)") (class "Default")
      (node (ref "R100") (pin "2") (pinfunction "2_2") (pintype "passive"))
      (node (ref "R97") (pin "1") (pinfunction "1_1") (pintype "passive"))
      (node (ref "U23") (pin "2") (pinfunction "+IN_2") (pintype "passive"))
    )
    (net (code "107") (name "Net-(U23-+OUT)") (class "Default")
      (node (ref "R109") (pin "2") (pinfunction "2_2") (pintype "passive"))
      (node (ref "U23") (pin "10") (pinfunction "+OUT_10") (pintype "passive"))
    )
    (net (code "108") (name "Net-(U23--IN)") (class "Default")
      (node (ref "R104") (pin "1") (pinfunction "1_1") (pintype "passive"))
      (node (ref "R99") (pin "2") (pinfunction "2_2") (pintype "passive"))
      (node (ref "U23") (pin "3") (pinfunction "-IN_3") (pintype "passive"))
    )
    (net (code "109") (name "Net-(U23--OUT)") (class "Default")
      (node (ref "R105") (pin "2") (pinfunction "2_2") (pintype "passive"))
      (node (ref "U23") (pin "11") (pinfunction "-OUT_11") (pintype "passive"))
    )
    (net (code "110") (name "Net-(U23-VOCM)") (class "Default")
      (node (ref "C60") (pin "1") (pinfunction "1_1") (pintype "passive"))
      (node (ref "R111") (pin "1") (pinfunction "1_1") (pintype "passive"))
      (node (ref "U23") (pin "9") (pinfunction "VOCM_9") (pintype "passive"))
    )
    (net (code "111") (name "Net-(U23-–FB)") (class "Default")
      (node (ref "R97") (pin "2") (pinfunction "2_2") (pintype "passive"))
      (node (ref "U23") (pin "1") (pinfunction "–FB_1") (pintype "passive"))
    )
    (net (code "112") (name "Net-(U24-+FB)") (class "Default")
      (node (ref "R107") (pin "2") (pinfunction "2_2") (pintype "passive"))
      (node (ref "U24") (pin "4") (pinfunction "+FB_4") (pintype "passive"))
    )
    (net (code "113") (name "Net-(U24-+IN)") (class "Default")
      (node (ref "R102") (pin "2") (pinfunction "2_2") (pintype "passive"))
      (node (ref "R98") (pin "1") (pinfunction "1_1") (pintype "passive"))
      (node (ref "U24") (pin "2") (pinfunction "+IN_2") (pintype "passive"))
    )
    (net (code "114") (name "Net-(U24-+OUT)") (class "Default")
      (node (ref "R110") (pin "2") (pinfunction "2_2") (pintype "passive"))
      (node (ref "U24") (pin "10") (pinfunction "+OUT_10") (pintype "passive"))
    )
    (net (code "115") (name "Net-(U24--IN)") (class "Default")
      (node (ref "R101") (pin "2") (pinfunction "2_2") (pintype "passive"))
      (node (ref "R107") (pin "1") (pinfunction "1_1") (pintype "passive"))
      (node (ref "U24") (pin "3") (pinfunction "-IN_3") (pintype "passive"))
    )
    (net (code "116") (name "Net-(U24--OUT)") (class "Default")
      (node (ref "R108") (pin "2") (pinfunction "2_2") (pintype "passive"))
      (node (ref "U24") (pin "11") (pinfunction "-OUT_11") (pintype "passive"))
    )
    (net (code "117") (name "Net-(U24-VOCM)") (class "Default")
      (node (ref "C61") (pin "1") (pinfunction "1_1") (pintype "passive"))
      (node (ref "R112") (pin "1") (pinfunction "1_1") (pintype "passive"))
      (node (ref "U24") (pin "9") (pinfunction "VOCM_9") (pintype "passive"))
    )
    (net (code "118") (name "Net-(U24-–FB)") (class "Default")
      (node (ref "R98") (pin "2") (pinfunction "2_2") (pintype "passive"))
      (node (ref "U24") (pin "1") (pinfunction "–FB_1") (pintype "passive"))
    )
    (net (code "119") (name "Net-(U27-+FB)") (class "Default")
      (node (ref "R121") (pin "2") (pinfunction "2_2") (pintype "passive"))
      (node (ref "U27") (pin "4") (pinfunction "+FB_4") (pintype "passive"))
    )
    (net (code "120") (name "Net-(U27-+IN)") (class "Default")
      (node (ref "R115") (pin "1") (pinfunction "1_1") (pintype "passive"))
      (node (ref "R117") (pin "2") (pinfunction "2_2") (pintype "passive"))
      (node (ref "U27") (pin "2") (pinfunction "+IN_2") (pintype "passive"))
    )
    (net (code "121") (name "Net-(U27-+OUT)") (class "Default")
      (node (ref "R127") (pin "2") (pinfunction "2_2") (pintype "passive"))
      (node (ref "U27") (pin "10") (pinfunction "+OUT_10") (pintype "passive"))
    )
    (net (code "122") (name "Net-(U27--IN)") (class "Default")
      (node (ref "R116") (pin "2") (pinfunction "2_2") (pintype "passive"))
      (node (ref "R121") (pin "1") (pinfunction "1_1") (pintype "passive"))
      (node (ref "U27") (pin "3") (pinfunction "-IN_3") (pintype "passive"))
    )
    (net (code "123") (name "Net-(U27--OUT)") (class "Default")
      (node (ref "R123") (pin "2") (pinfunction "2_2") (pintype "passive"))
      (node (ref "U27") (pin "11") (pinfunction "-OUT_11") (pintype "passive"))
    )
    (net (code "124") (name "Net-(U27-VOCM)") (class "Default")
      (node (ref "C64") (pin "1") (pinfunction "1_1") (pintype "passive"))
      (node (ref "R129") (pin "1") (pinfunction "1_1") (pintype "passive"))
      (node (ref "U27") (pin "9") (pinfunction "VOCM_9") (pintype "passive"))
    )
    (net (code "125") (name "Net-(U27-–FB)") (class "Default")
      (node (ref "R115") (pin "2") (pinfunction "2_2") (pintype "passive"))
      (node (ref "U27") (pin "1") (pinfunction "–FB_1") (pintype "passive"))
    )
    (net (code "126") (name "Net-(U28-+FB)") (class "Default")
      (node (ref "R125") (pin "2") (pinfunction "2_2") (pintype "passive"))
      (node (ref "U28") (pin "4") (pinfunction "+FB_4") (pintype "passive"))
    )
    (net (code "127") (name "Net-(U28-+IN)") (class "Default")
      (node (ref "R118") (pin "2") (pinfunction "2_2") (pintype "passive"))
      (node (ref "R119") (pin "1") (pinfunction "1_1") (pintype "passive"))
      (node (ref "U28") (pin "2") (pinfunction "+IN_2") (pintype "passive"))
    )
    (net (code "128") (name "Net-(U28-+OUT)") (class "Default")
      (node (ref "R128") (pin "2") (pinfunction "2_2") (pintype "passive"))
      (node (ref "U28") (pin "10") (pinfunction "+OUT_10") (pintype "passive"))
    )
    (net (code "129") (name "Net-(U28--IN)") (class "Default")
      (node (ref "R122") (pin "2") (pinfunction "2_2") (pintype "passive"))
      (node (ref "R125") (pin "1") (pinfunction "1_1") (pintype "passive"))
      (node (ref "U28") (pin "3") (pinfunction "-IN_3") (pintype "passive"))
    )
    (net (code "130") (name "Net-(U28--OUT)") (class "Default")
      (node (ref "R126") (pin "2") (pinfunction "2_2") (pintype "passive"))
      (node (ref "U28") (pin "11") (pinfunction "-OUT_11") (pintype "passive"))
    )
    (net (code "131") (name "Net-(U28-VOCM)") (class "Default")
      (node (ref "C65") (pin "1") (pinfunction "1_1") (pintype "passive"))
      (node (ref "R130") (pin "1") (pinfunction "1_1") (pintype "passive"))
      (node (ref "U28") (pin "9") (pinfunction "VOCM_9") (pintype "passive"))
    )
    (net (code "132") (name "Net-(U28-–FB)") (class "Default")
      (node (ref "R119") (pin "2") (pinfunction "2_2") (pintype "passive"))
      (node (ref "U28") (pin "1") (pinfunction "–FB_1") (pintype "passive"))
    )
    (net (code "133") (name "Net-(U57C-CLK+)") (class "Default")
      (node (ref "C66") (pin "1") (pinfunction "1_1") (pintype "passive"))
      (node (ref "R131") (pin "2") (pinfunction "2_2") (pintype "passive"))
      (node (ref "U57") (pin "1") (pinfunction "CLK+_1") (pintype "passive"))
    )
    (net (code "134") (name "Net-(U57C-CLK-)") (class "Default")
      (node (ref "C67") (pin "1") (pinfunction "1_1") (pintype "passive"))
      (node (ref "R131") (pin "1") (pinfunction "1_1") (pintype "passive"))
      (node (ref "U57") (pin "2") (pinfunction "CLK-_2") (pintype "passive"))
    )
    (net (code "135") (name "Net-(U58C-CLK+)") (class "Default")
      (node (ref "C73") (pin "1") (pinfunction "1_1") (pintype "passive"))
      (node (ref "R132") (pin "2") (pinfunction "2_2") (pintype "passive"))
      (node (ref "U58") (pin "1") (pinfunction "CLK+_1") (pintype "passive"))
    )
    (net (code "136") (name "Net-(U58C-CLK-)") (class "Default")
      (node (ref "C75") (pin "1") (pinfunction "1_1") (pintype "passive"))
      (node (ref "R132") (pin "1") (pinfunction "1_1") (pintype "passive"))
      (node (ref "U58") (pin "2") (pinfunction "CLK-_2") (pintype "passive"))
    )
    (net (code "137") (name "VEE_3V3") (class "Default")
      (node (ref "C152") (pin "2") (pinfunction "2_2") (pintype "passive"))
      (node (ref "C153") (pin "2") (pinfunction "2_2") (pintype "passive"))
      (node (ref "C154") (pin "2") (pinfunction "2_2") (pintype "passive"))
      (node (ref "C155") (pin "2") (pinfunction "2_2") (pintype "passive"))
      (node (ref "U23") (pin "13") (pinfunction "–VS_13") (pintype "passive"))
      (node (ref "U23") (pin "14") (pinfunction "–VS_14") (pintype "passive"))
      (node (ref "U23") (pin "15") (pinfunction "–VS_15") (pintype "passive"))
      (node (ref "U23") (pin "16") (pinfunction "–VS_16") (pintype "passive"))
      (node (ref "U24") (pin "13") (pinfunction "–VS_13") (pintype "passive"))
      (node (ref "U24") (pin "14") (pinfunction "–VS_14") (pintype "passive"))
      (node (ref "U24") (pin "15") (pinfunction "–VS_15") (pintype "passive"))
      (node (ref "U24") (pin "16") (pinfunction "–VS_16") (pintype "passive"))
      (node (ref "U27") (pin "13") (pinfunction "–VS_13") (pintype "passive"))
      (node (ref "U27") (pin "14") (pinfunction "–VS_14") (pintype "passive"))
      (node (ref "U27") (pin "15") (pinfunction "–VS_15") (pintype "passive"))
      (node (ref "U27") (pin "16") (pinfunction "–VS_16") (pintype "passive"))
      (node (ref "U28") (pin "13") (pinfunction "–VS_13") (pintype "passive"))
      (node (ref "U28") (pin "14") (pinfunction "–VS_14") (pintype "passive"))
      (node (ref "U28") (pin "15") (pinfunction "–VS_15") (pintype "passive"))
      (node (ref "U28") (pin "16") (pinfunction "–VS_16") (pintype "passive"))
    )
    (net (code "138") (name "unconnected-(U57C-DNC-Pad4)") (class "Default")
      (node (ref "U57") (pin "4") (pinfunction "DNC_4") (pintype "passive+no_connect"))
    )
    (net (code "139") (name "unconnected-(U57C-DNC-Pad5)") (class "Default")
      (node (ref "U57") (pin "5") (pinfunction "DNC_5") (pintype "passive+no_connect"))
    )
    (net (code "140") (name "unconnected-(U57C-DNC-Pad55)") (class "Default")
      (node (ref "U57") (pin "55") (pinfunction "DNC_55") (pintype "passive+no_connect"))
    )
    (net (code "141") (name "unconnected-(U57C-DNC-Pad56)") (class "Default")
      (node (ref "U57") (pin "56") (pinfunction "DNC_56") (pintype "passive+no_connect"))
    )
    (net (code "142") (name "unconnected-(U57C-DNC-Pad58)") (class "Default")
      (node (ref "U57") (pin "58") (pinfunction "DNC_58") (pintype "passive+no_connect"))
    )
    (net (code "143") (name "unconnected-(U58C-DNC-Pad4)") (class "Default")
      (node (ref "U58") (pin "4") (pinfunction "DNC_4") (pintype "passive+no_connect"))
    )
    (net (code "144") (name "unconnected-(U58C-DNC-Pad5)") (class "Default")
      (node (ref "U58") (pin "5") (pinfunction "DNC_5") (pintype "passive+no_connect"))
    )
    (net (code "145") (name "unconnected-(U58C-DNC-Pad55)") (class "Default")
      (node (ref "U58") (pin "55") (pinfunction "DNC_55") (pintype "passive+no_connect"))
    )
    (net (code "146") (name "unconnected-(U58C-DNC-Pad56)") (class "Default")
      (node (ref "U58") (pin "56") (pinfunction "DNC_56") (pintype "passive+no_connect"))
    )
    (net (code "147") (name "unconnected-(U58C-DNC-Pad58)") (class "Default")
      (node (ref "U58") (pin "58") (pinfunction "DNC_58") (pintype "passive+no_connect"))
    )
  )
)
